# antivape_testbench.net
KiCad netlist of a schematic drawn in Altium Designer
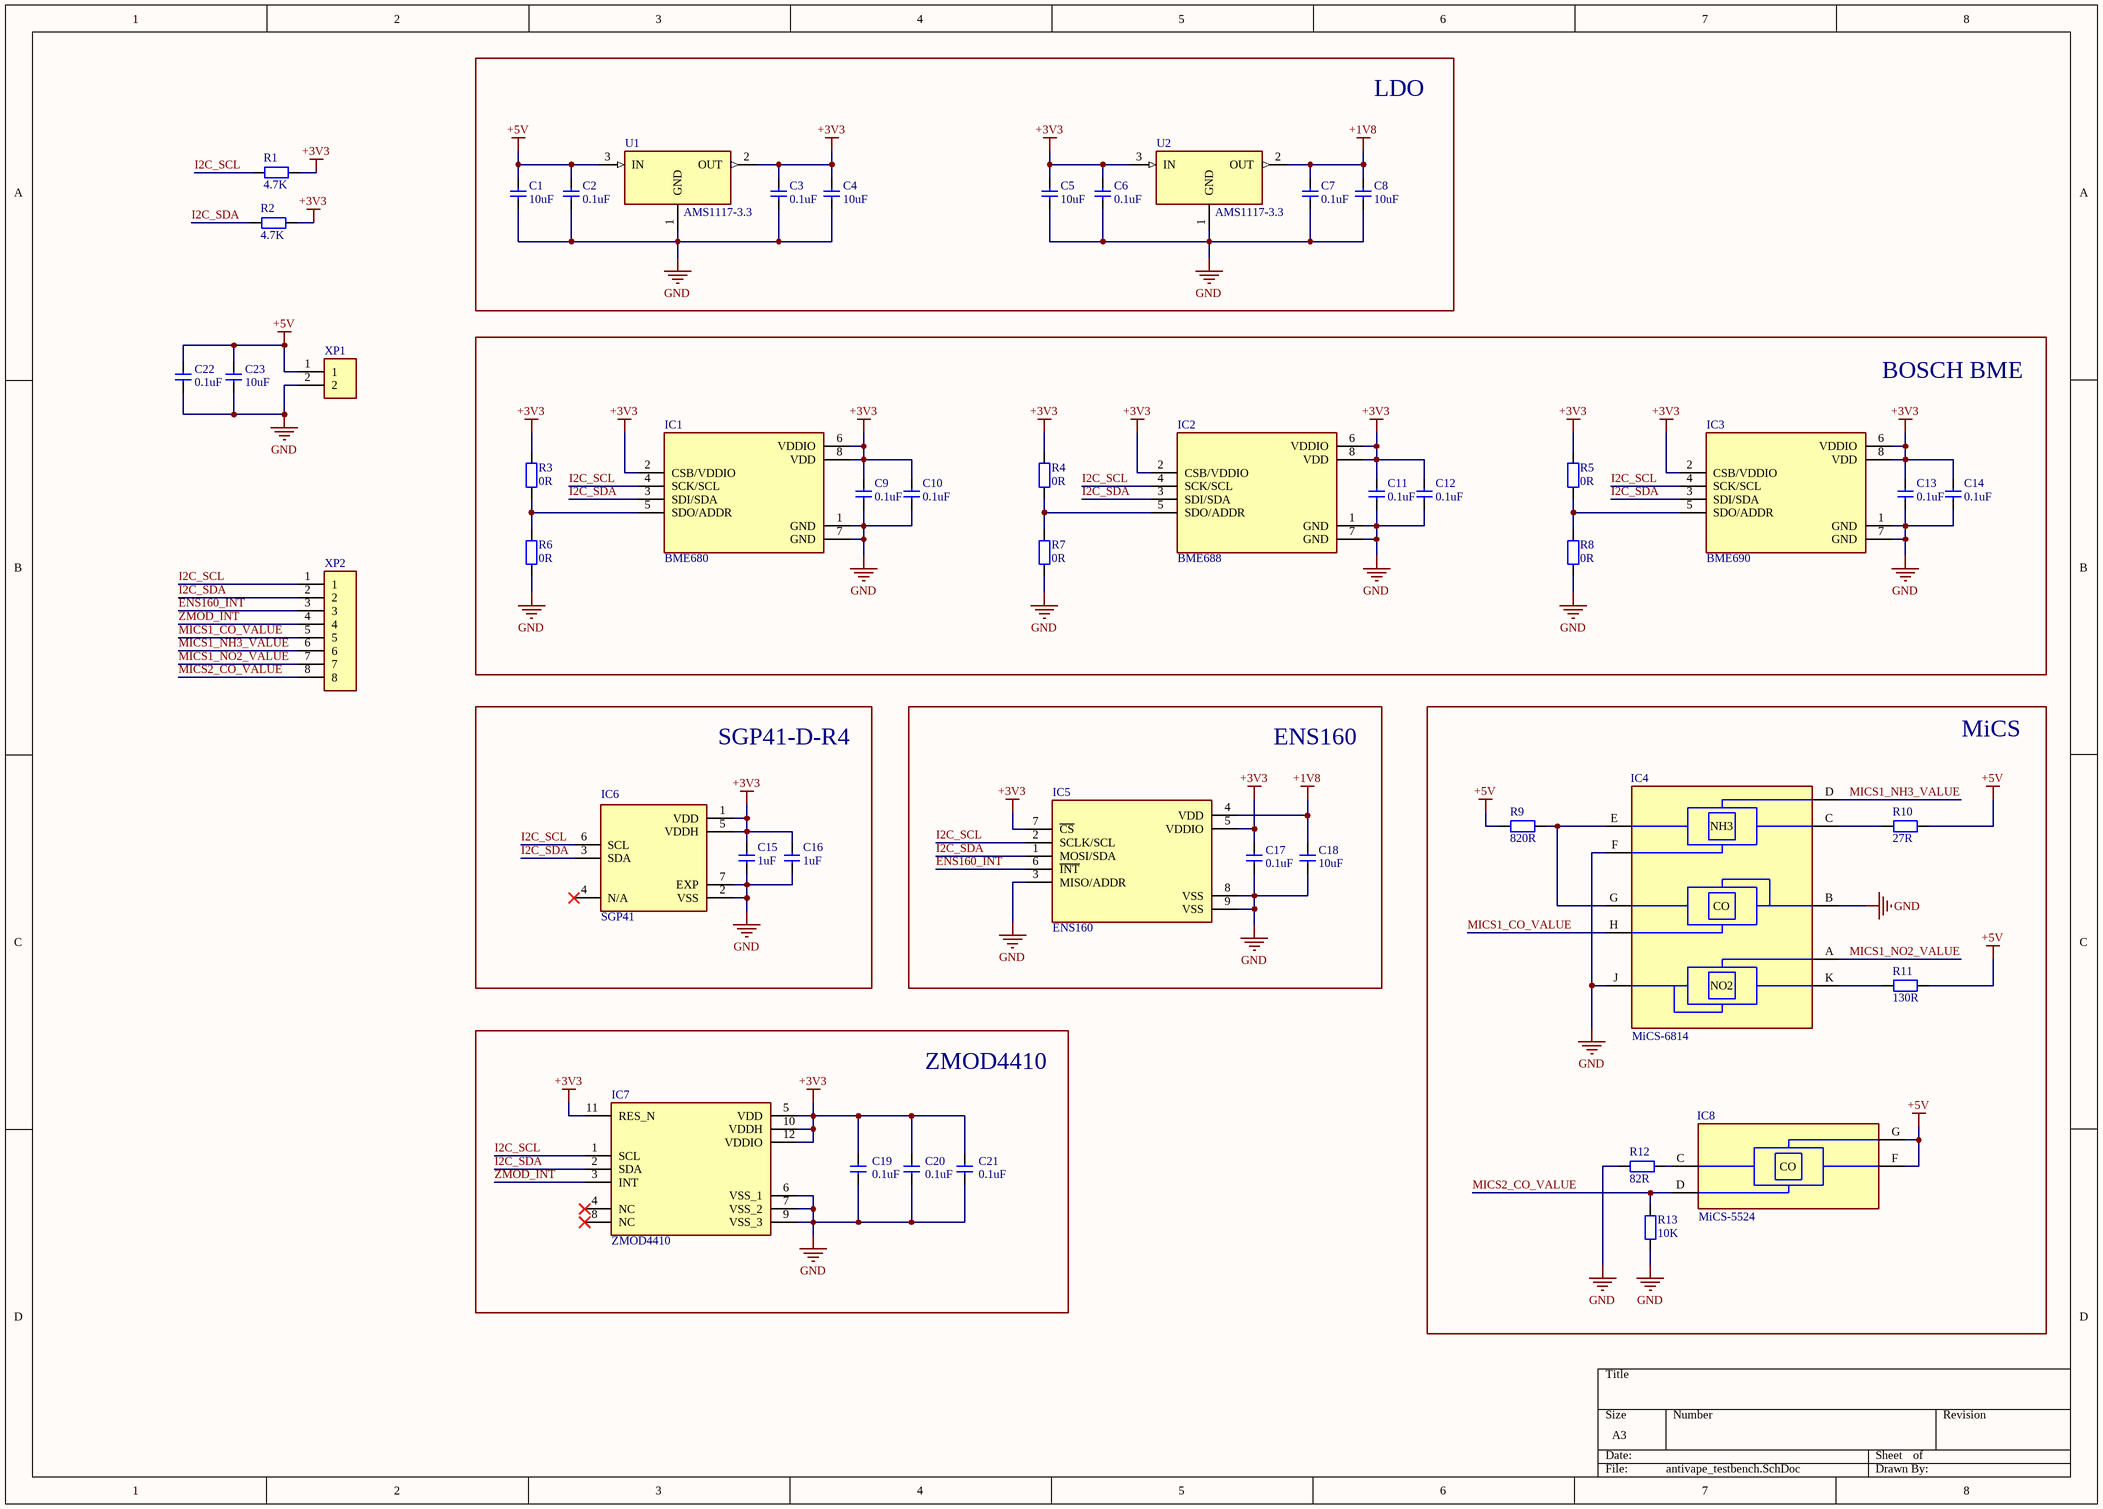
[diagram p0: antivape_testbench.SchDoc]

(export (version "E")
  (design (tool "Eeschema 10.0.6"))
  (components
    (comp (ref "C1")
      (value "10uF")
      (footprint "CAP0805")
      (description "Ceramic SMD Cap")
      (libsource (lib "Asterisk") (part "CAP Ceramic"))
    )
    (comp (ref "C2")
      (value "0.1uF")
      (footprint "CAP0805")
      (description "Ceramic SMD Cap")
      (libsource (lib "Asterisk") (part "CAP Ceramic"))
    )
    (comp (ref "C3")
      (value "0.1uF")
      (footprint "CAP0805")
      (description "Ceramic SMD Cap")
      (libsource (lib "Asterisk") (part "CAP Ceramic"))
    )
    (comp (ref "C4")
      (value "10uF")
      (footprint "CAP0805")
      (description "Ceramic SMD Cap")
      (libsource (lib "Asterisk") (part "CAP Ceramic"))
    )
    (comp (ref "C5")
      (value "10uF")
      (footprint "CAP0805")
      (description "Ceramic SMD Cap")
      (libsource (lib "Asterisk") (part "CAP Ceramic"))
    )
    (comp (ref "C6")
      (value "0.1uF")
      (footprint "CAP0805")
      (description "Ceramic SMD Cap")
      (libsource (lib "Asterisk") (part "CAP Ceramic"))
    )
    (comp (ref "C7")
      (value "0.1uF")
      (footprint "CAP0805")
      (description "Ceramic SMD Cap")
      (libsource (lib "Asterisk") (part "CAP Ceramic"))
    )
    (comp (ref "C8")
      (value "10uF")
      (footprint "CAP0805")
      (description "Ceramic SMD Cap")
      (libsource (lib "Asterisk") (part "CAP Ceramic"))
    )
    (comp (ref "C9")
      (value "0.1uF")
      (footprint "CAP0603")
      (description "Ceramic SMD Cap")
      (libsource (lib "Asterisk") (part "CAP Ceramic"))
    )
    (comp (ref "C10")
      (value "0.1uF")
      (footprint "CAP0603")
      (description "Ceramic SMD Cap")
      (libsource (lib "Asterisk") (part "CAP Ceramic"))
    )
    (comp (ref "C11")
      (value "0.1uF")
      (footprint "CAP0603")
      (description "Ceramic SMD Cap")
      (libsource (lib "Asterisk") (part "CAP Ceramic"))
    )
    (comp (ref "C12")
      (value "0.1uF")
      (footprint "CAP0603")
      (description "Ceramic SMD Cap")
      (libsource (lib "Asterisk") (part "CAP Ceramic"))
    )
    (comp (ref "C13")
      (value "0.1uF")
      (footprint "CAP0603")
      (description "Ceramic SMD Cap")
      (libsource (lib "Asterisk") (part "CAP Ceramic"))
    )
    (comp (ref "C14")
      (value "0.1uF")
      (footprint "CAP0603")
      (description "Ceramic SMD Cap")
      (libsource (lib "Asterisk") (part "CAP Ceramic"))
    )
    (comp (ref "C15")
      (value "1uF")
      (footprint "CAP0603")
      (description "Ceramic SMD Cap")
      (libsource (lib "Asterisk") (part "CAP Ceramic"))
    )
    (comp (ref "C16")
      (value "1uF")
      (footprint "CAP0603")
      (description "Ceramic SMD Cap")
      (libsource (lib "Asterisk") (part "CAP Ceramic"))
    )
    (comp (ref "C17")
      (value "0.1uF")
      (footprint "CAP0603")
      (description "Ceramic SMD Cap")
      (libsource (lib "Asterisk") (part "CAP Ceramic"))
    )
    (comp (ref "C18")
      (value "10uF")
      (footprint "CAP0805")
      (description "Ceramic SMD Cap")
      (libsource (lib "Asterisk") (part "CAP Ceramic"))
    )
    (comp (ref "C19")
      (value "0.1uF")
      (footprint "CAP0603")
      (description "Ceramic SMD Cap")
      (libsource (lib "Asterisk") (part "CAP Ceramic"))
    )
    (comp (ref "C20")
      (value "0.1uF")
      (footprint "CAP0603")
      (description "Ceramic SMD Cap")
      (libsource (lib "Asterisk") (part "CAP Ceramic"))
    )
    (comp (ref "C21")
      (value "0.1uF")
      (footprint "CAP0603")
      (description "Ceramic SMD Cap")
      (libsource (lib "Asterisk") (part "CAP Ceramic"))
    )
    (comp (ref "C22")
      (value "0.1uF")
      (footprint "CAP0805")
      (description "Ceramic SMD Cap")
      (libsource (lib "Asterisk") (part "CAP Ceramic"))
    )
    (comp (ref "C23")
      (value "10uF")
      (footprint "CAP0805")
      (description "Ceramic SMD Cap")
      (libsource (lib "Asterisk") (part "CAP Ceramic"))
    )
    (comp (ref "IC1") (value "BME680") (footprint "BMEXXX") (libsource (lib "Asterisk") (part "BME680")))
    (comp (ref "IC2") (value "BME688") (footprint "BMEXXX") (libsource (lib "Asterisk") (part "BME688")))
    (comp (ref "IC3") (value "BME690") (footprint "BMEXXX") (libsource (lib "Asterisk") (part "BME690")))
    (comp (ref "IC4")
      (value "MiCS-6814")
      (footprint "MiCS-6814")
      (libsource (lib "Asterisk") (part "MiCS-6814"))
    )
    (comp (ref "IC5") (value "ENS160") (footprint "ENS160") (libsource (lib "Asterisk") (part "ENS160")))
    (comp (ref "IC6")
      (value "SGP41")
      (footprint "SGP41-D-R4")
      (libsource (lib "Asterisk") (part "SGP41-D-R4"))
    )
    (comp (ref "IC7")
      (value "ZMOD4410")
      (footprint "ZMOD4410")
      (libsource (lib "Asterisk") (part "ZMOD4410"))
    )
    (comp (ref "IC8")
      (value "MiCS-5524")
      (footprint "MiCS-6814")
      (libsource (lib "Asterisk") (part "MiCS-5524"))
    )
    (comp (ref "R1")
      (value "4.7K")
      (footprint "RES0603")
      (description "RES smd")
      (libsource (lib "") (part "RES_1"))
    )
    (comp (ref "R2")
      (value "4.7K")
      (footprint "RES0603")
      (description "RES smd")
      (libsource (lib "Asterisk") (part "RES"))
    )
    (comp (ref "R3")
      (value "0R")
      (footprint "RES0603")
      (description "RES smd")
      (libsource (lib "Asterisk") (part "RES"))
    )
    (comp (ref "R4")
      (value "0R")
      (footprint "RES0603")
      (description "RES smd")
      (libsource (lib "Asterisk") (part "RES"))
    )
    (comp (ref "R5")
      (value "0R")
      (footprint "RES0603")
      (description "RES smd")
      (libsource (lib "Asterisk") (part "RES"))
    )
    (comp (ref "R6")
      (value "0R")
      (footprint "RES0603")
      (description "RES smd")
      (libsource (lib "Asterisk") (part "RES"))
    )
    (comp (ref "R7")
      (value "0R")
      (footprint "RES0603")
      (description "RES smd")
      (libsource (lib "Asterisk") (part "RES"))
    )
    (comp (ref "R8")
      (value "0R")
      (footprint "RES0603")
      (description "RES smd")
      (libsource (lib "Asterisk") (part "RES"))
    )
    (comp (ref "R9")
      (value "820R")
      (footprint "RES0805")
      (description "RES smd")
      (libsource (lib "Asterisk") (part "RES"))
    )
    (comp (ref "R10")
      (value "27R")
      (footprint "RES0805")
      (description "RES smd")
      (libsource (lib "Asterisk") (part "RES"))
    )
    (comp (ref "R11")
      (value "130R")
      (footprint "RES0805")
      (description "RES smd")
      (libsource (lib "Asterisk") (part "RES"))
    )
    (comp (ref "R12")
      (value "82R")
      (footprint "RES0805")
      (description "RES smd")
      (libsource (lib "Asterisk") (part "RES"))
    )
    (comp (ref "R13")
      (value "10K")
      (footprint "RES0805")
      (description "RES smd")
      (libsource (lib "Asterisk") (part "RES"))
    )
    (comp (ref "U1")
      (value "AMS1117-3.3")
      (footprint "SOT-223")
      (description "Linear voltage regulator")
      (libsource (lib "Asterisk") (part "AMS1117"))
    )
    (comp (ref "U2")
      (value "AMS1117-3.3")
      (footprint "SOT-223")
      (description "Linear voltage regulator")
      (libsource (lib "Asterisk") (part "AMS1117"))
    )
    (comp (ref "XP1") (value "Conn-2") (footprint "PLS-2") (libsource (lib "Asterisk") (part "Conn-2")))
    (comp (ref "XP2") (value "Conn-8") (footprint "PLS 8x2.54") (libsource (lib "Asterisk") (part "Conn-8")))
  )
  (nets
    (net (code "1") (name "+1V8") (class "Default")
      (node (ref "C18") (pin "2") (pinfunction "2_2") (pintype "passive"))
      (node (ref "C7") (pin "2") (pinfunction "2_2") (pintype "passive"))
      (node (ref "C8") (pin "2") (pinfunction "2_2") (pintype "passive"))
      (node (ref "IC5") (pin "4") (pinfunction "VDD_4") (pintype "passive"))
      (node (ref "U2") (pin "2") (pinfunction "OUT_2") (pintype "output"))
    )
    (net (code "2") (name "+3V3") (class "Default")
      (node (ref "C10") (pin "2") (pinfunction "2_2") (pintype "passive"))
      (node (ref "C11") (pin "2") (pinfunction "2_2") (pintype "passive"))
      (node (ref "C12") (pin "2") (pinfunction "2_2") (pintype "passive"))
      (node (ref "C13") (pin "2") (pinfunction "2_2") (pintype "passive"))
      (node (ref "C14") (pin "2") (pinfunction "2_2") (pintype "passive"))
      (node (ref "C15") (pin "2") (pinfunction "2_2") (pintype "passive"))
      (node (ref "C16") (pin "2") (pinfunction "2_2") (pintype "passive"))
      (node (ref "C17") (pin "2") (pinfunction "2_2") (pintype "passive"))
      (node (ref "C19") (pin "2") (pinfunction "2_2") (pintype "passive"))
      (node (ref "C20") (pin "2") (pinfunction "2_2") (pintype "passive"))
      (node (ref "C21") (pin "2") (pinfunction "2_2") (pintype "passive"))
      (node (ref "C3") (pin "2") (pinfunction "2_2") (pintype "passive"))
      (node (ref "C4") (pin "2") (pinfunction "2_2") (pintype "passive"))
      (node (ref "C5") (pin "2") (pinfunction "2_2") (pintype "passive"))
      (node (ref "C6") (pin "2") (pinfunction "2_2") (pintype "passive"))
      (node (ref "C9") (pin "2") (pinfunction "2_2") (pintype "passive"))
      (node (ref "IC1") (pin "2") (pinfunction "CSB/VDDIO_2") (pintype "passive"))
      (node (ref "IC1") (pin "6") (pinfunction "VDDIO_6") (pintype "power_in"))
      (node (ref "IC1") (pin "8") (pinfunction "VDD_8") (pintype "power_in"))
      (node (ref "IC2") (pin "2") (pinfunction "CSB/VDDIO_2") (pintype "passive"))
      (node (ref "IC2") (pin "6") (pinfunction "VDDIO_6") (pintype "power_in"))
      (node (ref "IC2") (pin "8") (pinfunction "VDD_8") (pintype "power_in"))
      (node (ref "IC3") (pin "2") (pinfunction "CSB/VDDIO_2") (pintype "passive"))
      (node (ref "IC3") (pin "6") (pinfunction "VDDIO_6") (pintype "power_in"))
      (node (ref "IC3") (pin "8") (pinfunction "VDD_8") (pintype "power_in"))
      (node (ref "IC5") (pin "5") (pinfunction "VDDIO_5") (pintype "passive"))
      (node (ref "IC5") (pin "7") (pinfunction "~{CS}_7") (pintype "passive"))
      (node (ref "IC6") (pin "1") (pinfunction "VDD_1") (pintype "passive"))
      (node (ref "IC6") (pin "5") (pinfunction "VDDH_5") (pintype "passive"))
      (node (ref "IC7") (pin "10") (pinfunction "VDDH_10") (pintype "passive"))
      (node (ref "IC7") (pin "11") (pinfunction "RES_N_11") (pintype "passive"))
      (node (ref "IC7") (pin "12") (pinfunction "VDDIO_12") (pintype "passive"))
      (node (ref "IC7") (pin "5") (pinfunction "VDD_5") (pintype "passive"))
      (node (ref "R1") (pin "2") (pinfunction "2_2") (pintype "passive"))
      (node (ref "R2") (pin "2") (pinfunction "2_2") (pintype "passive"))
      (node (ref "R3") (pin "2") (pinfunction "2_2") (pintype "passive"))
      (node (ref "R4") (pin "2") (pinfunction "2_2") (pintype "passive"))
      (node (ref "R5") (pin "2") (pinfunction "2_2") (pintype "passive"))
      (node (ref "U1") (pin "2") (pinfunction "OUT_2") (pintype "output"))
      (node (ref "U2") (pin "3") (pinfunction "IN_3") (pintype "input"))
    )
    (net (code "3") (name "+5V") (class "Default")
      (node (ref "C1") (pin "2") (pinfunction "2_2") (pintype "passive"))
      (node (ref "C2") (pin "2") (pinfunction "2_2") (pintype "passive"))
      (node (ref "C22") (pin "2") (pinfunction "2_2") (pintype "passive"))
      (node (ref "C23") (pin "2") (pinfunction "2_2") (pintype "passive"))
      (node (ref "IC8") (pin "F") (pinfunction "RH1/RS1_RED_F") (pintype "passive"))
      (node (ref "IC8") (pin "G") (pinfunction "RS1_NH3_G") (pintype "passive"))
      (node (ref "R10") (pin "2") (pinfunction "2_2") (pintype "passive"))
      (node (ref "R11") (pin "2") (pinfunction "2_2") (pintype "passive"))
      (node (ref "R9") (pin "1") (pinfunction "1_1") (pintype "passive"))
      (node (ref "U1") (pin "3") (pinfunction "IN_3") (pintype "input"))
      (node (ref "XP1") (pin "1") (pinfunction "1_1") (pintype "passive"))
    )
    (net (code "4") (name "/ENS160_INT") (class "Default")
      (node (ref "IC5") (pin "6") (pinfunction "~{INT}_6") (pintype "passive"))
      (node (ref "XP2") (pin "3") (pinfunction "3_3") (pintype "passive"))
    )
    (net (code "5") (name "/I2C_SCL") (class "Default")
      (node (ref "IC1") (pin "4") (pinfunction "SCK/SCL_4") (pintype "passive"))
      (node (ref "IC2") (pin "4") (pinfunction "SCK/SCL_4") (pintype "passive"))
      (node (ref "IC3") (pin "4") (pinfunction "SCK/SCL_4") (pintype "passive"))
      (node (ref "IC5") (pin "2") (pinfunction "SCLK/SCL_2") (pintype "passive"))
      (node (ref "IC6") (pin "6") (pinfunction "SCL_6") (pintype "passive"))
      (node (ref "IC7") (pin "1") (pinfunction "SCL_1") (pintype "passive"))
      (node (ref "R1") (pin "1") (pinfunction "1_1") (pintype "passive"))
      (node (ref "XP2") (pin "1") (pinfunction "1_1") (pintype "passive"))
    )
    (net (code "6") (name "/I2C_SDA") (class "Default")
      (node (ref "IC1") (pin "3") (pinfunction "SDI/SDA_3") (pintype "passive"))
      (node (ref "IC2") (pin "3") (pinfunction "SDI/SDA_3") (pintype "passive"))
      (node (ref "IC3") (pin "3") (pinfunction "SDI/SDA_3") (pintype "passive"))
      (node (ref "IC5") (pin "1") (pinfunction "MOSI/SDA_1") (pintype "passive"))
      (node (ref "IC6") (pin "3") (pinfunction "SDA_3") (pintype "passive"))
      (node (ref "IC7") (pin "2") (pinfunction "SDA_2") (pintype "passive"))
      (node (ref "R2") (pin "1") (pinfunction "1_1") (pintype "passive"))
      (node (ref "XP2") (pin "2") (pinfunction "2_2") (pintype "passive"))
    )
    (net (code "7") (name "/MICS1_CO_VALUE") (class "Default")
      (node (ref "IC4") (pin "H") (pinfunction "RS2_RED_H") (pintype "passive"))
      (node (ref "XP2") (pin "5") (pinfunction "5_5") (pintype "passive"))
    )
    (net (code "8") (name "/MICS1_NH3_VALUE") (class "Default")
      (node (ref "IC4") (pin "D") (pinfunction "RS1_NH3_D") (pintype "passive"))
      (node (ref "XP2") (pin "6") (pinfunction "6_6") (pintype "passive"))
    )
    (net (code "9") (name "/MICS1_NO2_VALUE") (class "Default")
      (node (ref "IC4") (pin "A") (pinfunction "RS2_A") (pintype "passive"))
      (node (ref "XP2") (pin "7") (pinfunction "7_7") (pintype "passive"))
    )
    (net (code "10") (name "/MICS2_CO_VALUE") (class "Default")
      (node (ref "IC8") (pin "D") (pinfunction "RS2_RED_D") (pintype "passive"))
      (node (ref "R13") (pin "2") (pinfunction "2_2") (pintype "passive"))
      (node (ref "XP2") (pin "8") (pinfunction "8_8") (pintype "passive"))
    )
    (net (code "11") (name "/ZMOD_INT") (class "Default")
      (node (ref "IC7") (pin "3") (pinfunction "INT_3") (pintype "passive"))
      (node (ref "XP2") (pin "4") (pinfunction "4_4") (pintype "passive"))
    )
    (net (code "12") (name "GND") (class "Default")
      (node (ref "C1") (pin "1") (pinfunction "1_1") (pintype "passive"))
      (node (ref "C10") (pin "1") (pinfunction "1_1") (pintype "passive"))
      (node (ref "C11") (pin "1") (pinfunction "1_1") (pintype "passive"))
      (node (ref "C12") (pin "1") (pinfunction "1_1") (pintype "passive"))
      (node (ref "C13") (pin "1") (pinfunction "1_1") (pintype "passive"))
      (node (ref "C14") (pin "1") (pinfunction "1_1") (pintype "passive"))
      (node (ref "C15") (pin "1") (pinfunction "1_1") (pintype "passive"))
      (node (ref "C16") (pin "1") (pinfunction "1_1") (pintype "passive"))
      (node (ref "C17") (pin "1") (pinfunction "1_1") (pintype "passive"))
      (node (ref "C18") (pin "1") (pinfunction "1_1") (pintype "passive"))
      (node (ref "C19") (pin "1") (pinfunction "1_1") (pintype "passive"))
      (node (ref "C2") (pin "1") (pinfunction "1_1") (pintype "passive"))
      (node (ref "C20") (pin "1") (pinfunction "1_1") (pintype "passive"))
      (node (ref "C21") (pin "1") (pinfunction "1_1") (pintype "passive"))
      (node (ref "C22") (pin "1") (pinfunction "1_1") (pintype "passive"))
      (node (ref "C23") (pin "1") (pinfunction "1_1") (pintype "passive"))
      (node (ref "C3") (pin "1") (pinfunction "1_1") (pintype "passive"))
      (node (ref "C4") (pin "1") (pinfunction "1_1") (pintype "passive"))
      (node (ref "C5") (pin "1") (pinfunction "1_1") (pintype "passive"))
      (node (ref "C6") (pin "1") (pinfunction "1_1") (pintype "passive"))
      (node (ref "C7") (pin "1") (pinfunction "1_1") (pintype "passive"))
      (node (ref "C8") (pin "1") (pinfunction "1_1") (pintype "passive"))
      (node (ref "C9") (pin "1") (pinfunction "1_1") (pintype "passive"))
      (node (ref "IC1") (pin "1") (pinfunction "GND_1") (pintype "power_in"))
      (node (ref "IC1") (pin "7") (pinfunction "GND_7") (pintype "power_in"))
      (node (ref "IC2") (pin "1") (pinfunction "GND_1") (pintype "power_in"))
      (node (ref "IC2") (pin "7") (pinfunction "GND_7") (pintype "power_in"))
      (node (ref "IC3") (pin "1") (pinfunction "GND_1") (pintype "power_in"))
      (node (ref "IC3") (pin "7") (pinfunction "GND_7") (pintype "power_in"))
      (node (ref "IC4") (pin "B") (pinfunction "RH1/RS1_RED_B") (pintype "passive"))
      (node (ref "IC4") (pin "F") (pinfunction "RS2_NH3_F") (pintype "passive"))
      (node (ref "IC4") (pin "J") (pinfunction "RH1/RS1_OX_J") (pintype "passive"))
      (node (ref "IC5") (pin "3") (pinfunction "MISO/ADDR_3") (pintype "passive"))
      (node (ref "IC5") (pin "8") (pinfunction "VSS_8") (pintype "passive"))
      (node (ref "IC5") (pin "9") (pinfunction "VSS_9") (pintype "passive"))
      (node (ref "IC6") (pin "2") (pinfunction "VSS_2") (pintype "passive"))
      (node (ref "IC6") (pin "7") (pinfunction "EXP_7") (pintype "passive"))
      (node (ref "IC7") (pin "6") (pinfunction "VSS_1_6") (pintype "passive"))
      (node (ref "IC7") (pin "7") (pinfunction "VSS_2_7") (pintype "passive"))
      (node (ref "IC7") (pin "9") (pinfunction "VSS_3_9") (pintype "passive"))
      (node (ref "R12") (pin "1") (pinfunction "1_1") (pintype "passive"))
      (node (ref "R13") (pin "1") (pinfunction "1_1") (pintype "passive"))
      (node (ref "R6") (pin "1") (pinfunction "1_1") (pintype "passive"))
      (node (ref "R7") (pin "1") (pinfunction "1_1") (pintype "passive"))
      (node (ref "R8") (pin "1") (pinfunction "1_1") (pintype "passive"))
      (node (ref "U1") (pin "1") (pinfunction "GND_1") (pintype "power_in"))
      (node (ref "U2") (pin "1") (pinfunction "GND_1") (pintype "power_in"))
      (node (ref "XP1") (pin "2") (pinfunction "2_2") (pintype "passive"))
    )
    (net (code "13") (name "Net-(IC1-SDO{slash}ADDR)") (class "Default")
      (node (ref "IC1") (pin "5") (pinfunction "SDO/ADDR_5") (pintype "passive"))
      (node (ref "R3") (pin "1") (pinfunction "1_1") (pintype "passive"))
      (node (ref "R6") (pin "2") (pinfunction "2_2") (pintype "passive"))
    )
    (net (code "14") (name "Net-(IC2-SDO{slash}ADDR)") (class "Default")
      (node (ref "IC2") (pin "5") (pinfunction "SDO/ADDR_5") (pintype "passive"))
      (node (ref "R4") (pin "1") (pinfunction "1_1") (pintype "passive"))
      (node (ref "R7") (pin "2") (pinfunction "2_2") (pintype "passive"))
    )
    (net (code "15") (name "Net-(IC3-SDO{slash}ADDR)") (class "Default")
      (node (ref "IC3") (pin "5") (pinfunction "SDO/ADDR_5") (pintype "passive"))
      (node (ref "R5") (pin "1") (pinfunction "1_1") (pintype "passive"))
      (node (ref "R8") (pin "2") (pinfunction "2_2") (pintype "passive"))
    )
    (net (code "16") (name "Net-(IC4-RH1_NH3)") (class "Default")
      (node (ref "IC4") (pin "C") (pinfunction "RH1_NH3_C") (pintype "passive"))
      (node (ref "R10") (pin "1") (pinfunction "1_1") (pintype "passive"))
    )
    (net (code "17") (name "Net-(IC4-RH2_NH3)") (class "Default")
      (node (ref "IC4") (pin "E") (pinfunction "RH2_NH3_E") (pintype "passive"))
      (node (ref "IC4") (pin "G") (pinfunction "RH2_RED_G") (pintype "passive"))
      (node (ref "R9") (pin "2") (pinfunction "2_2") (pintype "passive"))
    )
    (net (code "18") (name "Net-(IC4-RH2_OX)") (class "Default")
      (node (ref "IC4") (pin "K") (pinfunction "RH2_OX_K") (pintype "passive"))
      (node (ref "R11") (pin "1") (pinfunction "1_1") (pintype "passive"))
    )
    (net (code "19") (name "Net-(IC8-RH2_RED)") (class "Default")
      (node (ref "IC8") (pin "C") (pinfunction "RH2_RED_C") (pintype "passive"))
      (node (ref "R12") (pin "2") (pinfunction "2_2") (pintype "passive"))
    )
    (net (code "20") (name "unconnected-(IC6-N{slash}A-Pad4)") (class "Default")
      (node (ref "IC6") (pin "4") (pinfunction "N/A_4") (pintype "passive+no_connect"))
    )
    (net (code "21") (name "unconnected-(IC7-NC-Pad4)") (class "Default")
      (node (ref "IC7") (pin "4") (pinfunction "NC_4") (pintype "passive+no_connect"))
    )
    (net (code "22") (name "unconnected-(IC7-NC-Pad8)") (class "Default")
      (node (ref "IC7") (pin "8") (pinfunction "NC_8") (pintype "passive+no_connect"))
    )
  )
)
